# PowerSuply_Schematic_ETCautoPrikratki.net
KiCad netlist of a schematic drawn in EasyEDA
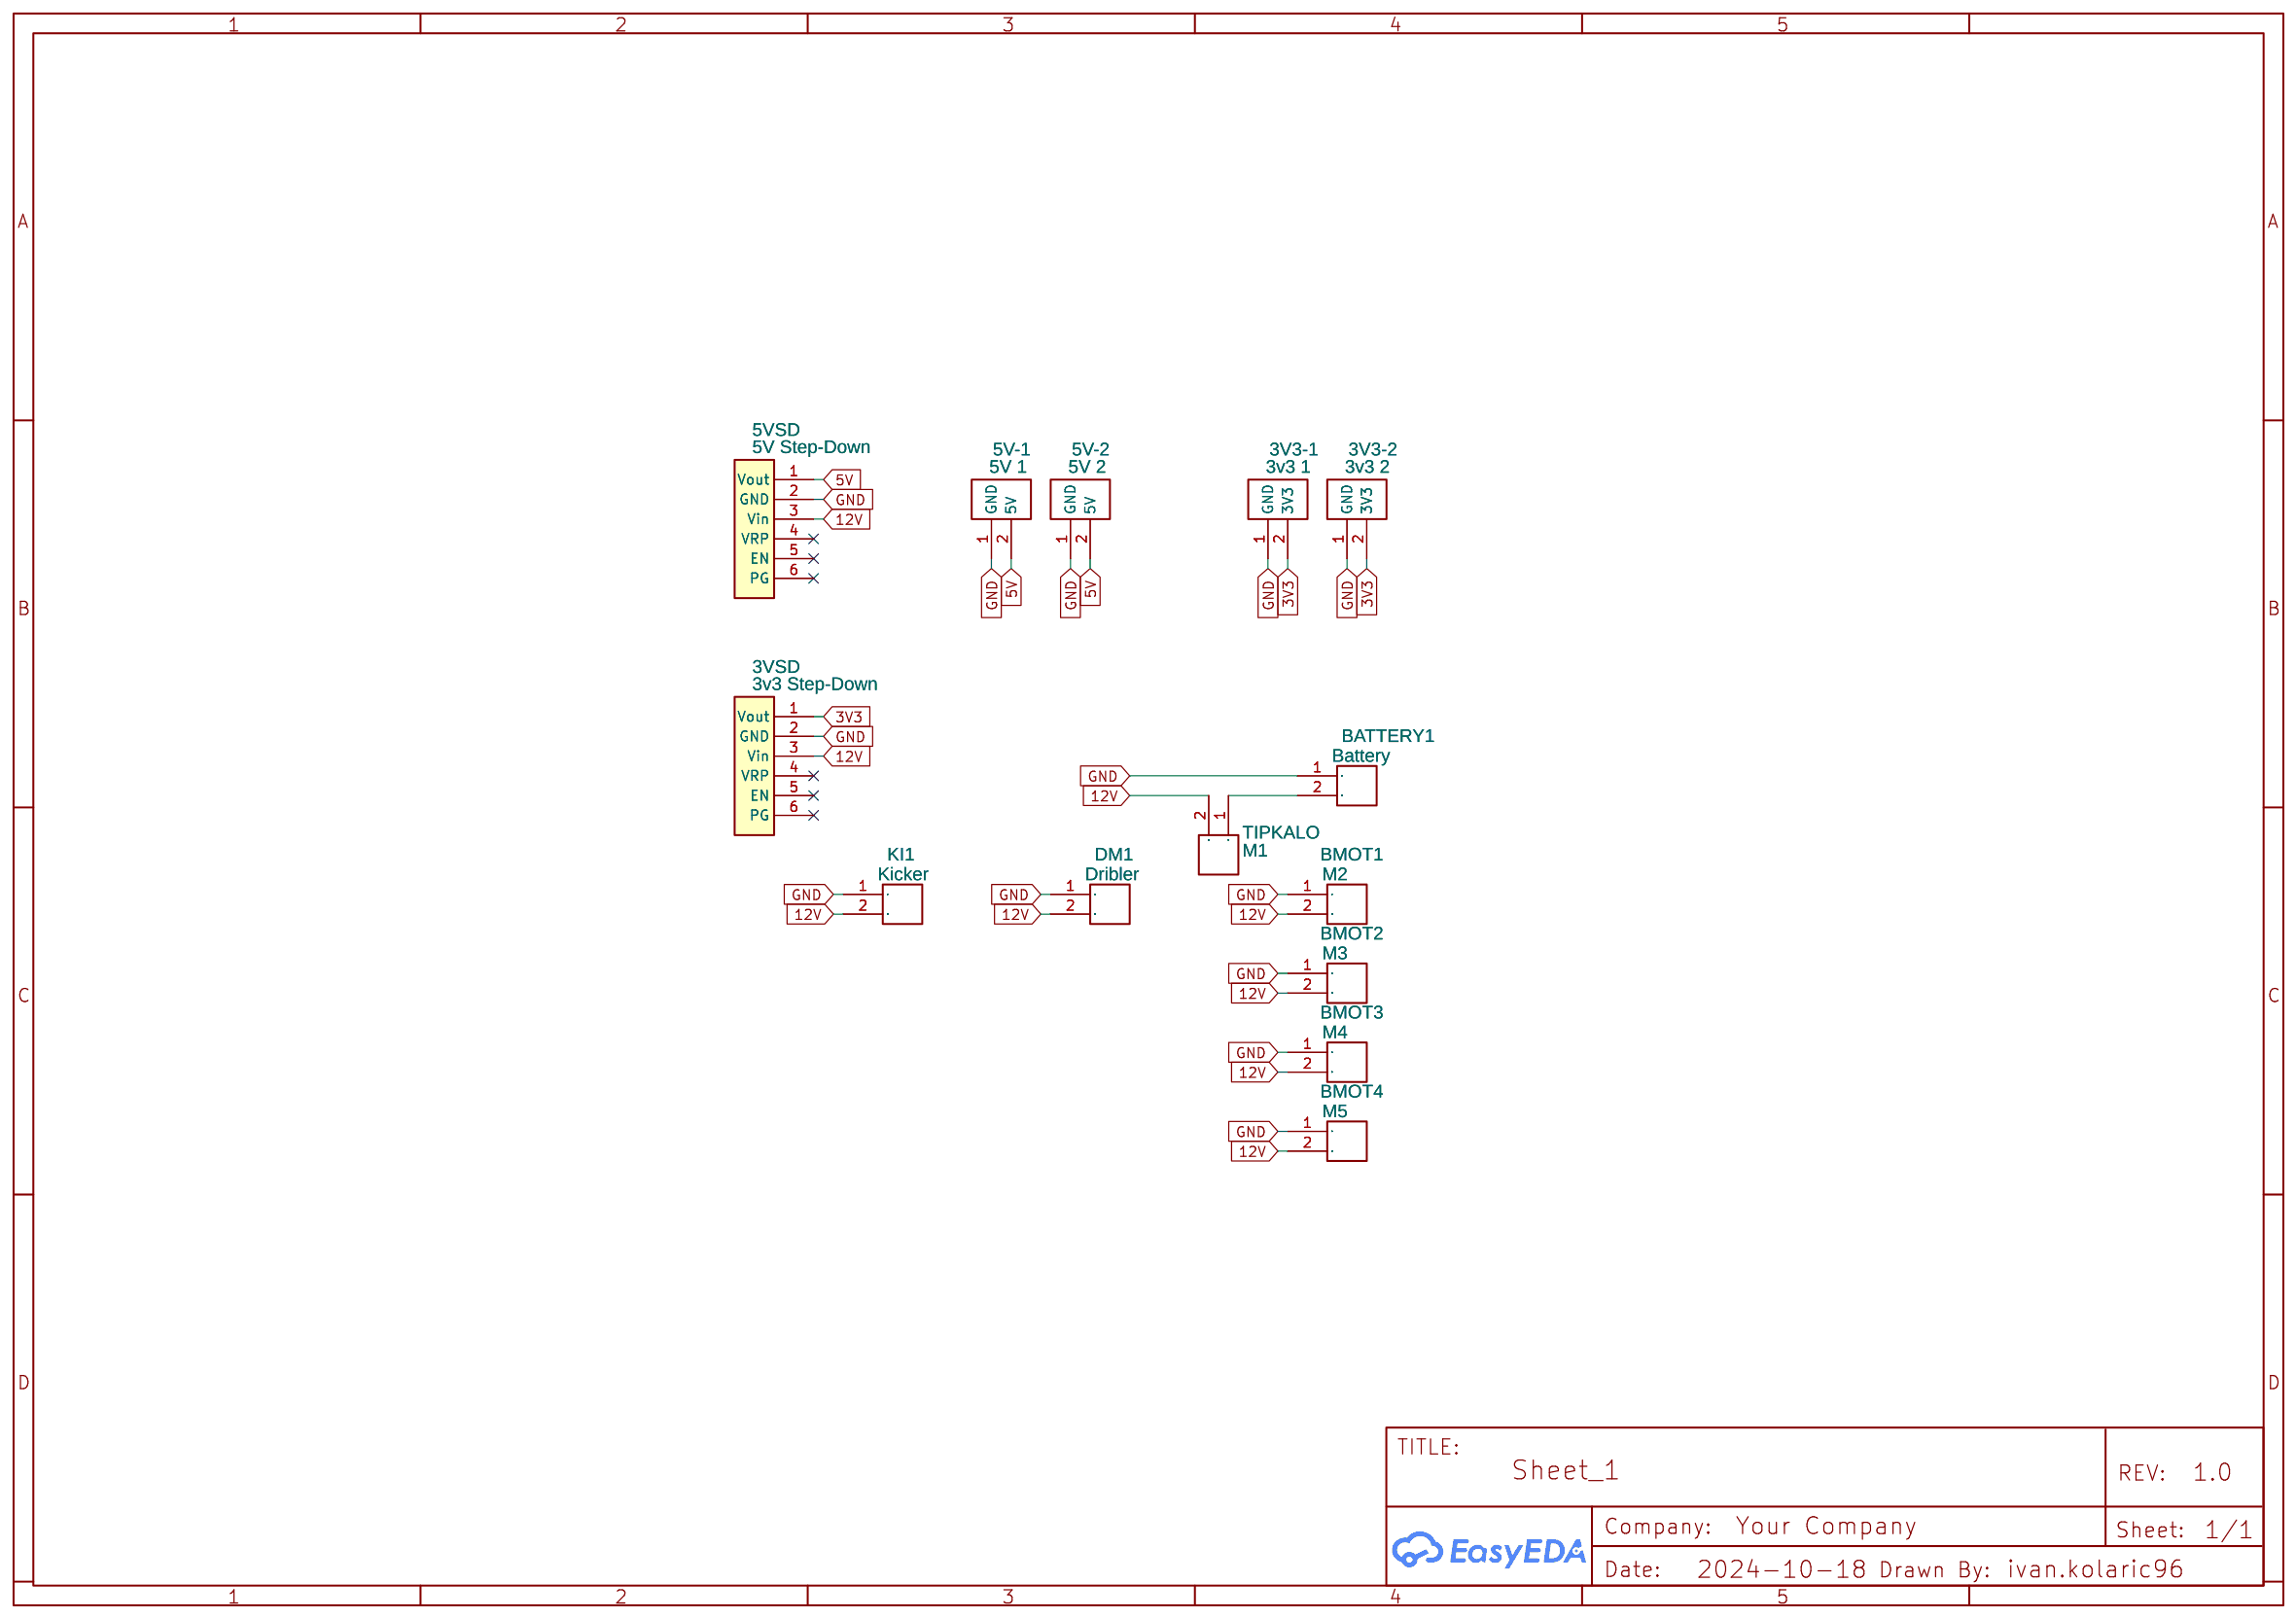
[diagram p0: schematic sheet]

(export (version "E")
  (design (tool "Eeschema 10.0.6"))
  (components
    (comp (ref "3V3-1")
      (value "3v3 1")
      (fields (field (name "Manufacturer Part") "22-11-2022") (field (name "Manufacturer") "MOLEX"))
      (libsource (lib "") (part "MOLEX_KK254_2P VERT._1"))
    )
    (comp (ref "3V3-2")
      (value "3v3 2")
      (fields (field (name "Manufacturer Part") "22-11-2022") (field (name "Manufacturer") "MOLEX"))
      (libsource (lib "") (part "MOLEX_KK254_2P VERT._1"))
    )
    (comp (ref "3VSD") (value "3v3 Step-Down") (libsource (lib "") (part "STEP-DOWN POLOLU D36V50F5_1")))
    (comp (ref "5V-1")
      (value "5V 1")
      (fields (field (name "Manufacturer Part") "22-11-2022") (field (name "Manufacturer") "MOLEX"))
      (libsource (lib "") (part "MOLEX_KK254_2P VERT."))
    )
    (comp (ref "5V-2")
      (value "5V 2")
      (fields (field (name "Manufacturer Part") "22-11-2022") (field (name "Manufacturer") "MOLEX"))
      (libsource (lib "") (part "MOLEX_KK254_2P VERT."))
    )
    (comp (ref "5VSD") (value "5V Step-Down") (libsource (lib "") (part "STEP-DOWN POLOLU D36V50F5")))
    (comp (ref "BATTERY1") (value "Battery") (libsource (lib "") (part "Molex KKK396 2 Pin_4")))
    (comp (ref "BMOT1") (value "M2") (libsource (lib "") (part "Molex KKK396 2 Pin_1")))
    (comp (ref "BMOT2") (value "M3") (libsource (lib "") (part "Molex KKK396 2 Pin_1")))
    (comp (ref "BMOT3") (value "M4") (libsource (lib "") (part "Molex KKK396 2 Pin_1")))
    (comp (ref "BMOT4") (value "M5") (libsource (lib "") (part "Molex KKK396 2 Pin_1")))
    (comp (ref "DM1") (value "Dribler") (libsource (lib "") (part "Molex KKK396 2 Pin")))
    (comp (ref "KI1") (value "Kicker") (libsource (lib "") (part "Molex KKK396 2 Pin_3")))
    (comp (ref "TIPKALO") (value "M1") (libsource (lib "") (part "Molex KKK396 2 Pin_2")))
  )
  (nets
    (net (code "1") (name "3V3") (class "Default")
      (node (ref "3V3-1") (pin "2") (pinfunction "3V3_2") (pintype "unspecified"))
      (node (ref "3V3-2") (pin "2") (pinfunction "3V3_2") (pintype "unspecified"))
      (node (ref "3VSD") (pin "1") (pinfunction "Vout_1") (pintype "unspecified"))
    )
    (net (code "2") (name "5V") (class "Default")
      (node (ref "5V-1") (pin "2") (pinfunction "5V_2") (pintype "unspecified"))
      (node (ref "5V-2") (pin "2") (pinfunction "5V_2") (pintype "unspecified"))
      (node (ref "5VSD") (pin "1") (pinfunction "Vout_1") (pintype "unspecified"))
    )
    (net (code "3") (name "12V") (class "Default")
      (node (ref "3VSD") (pin "3") (pinfunction "Vin_3") (pintype "unspecified"))
      (node (ref "5VSD") (pin "3") (pinfunction "Vin_3") (pintype "unspecified"))
      (node (ref "BMOT1") (pin "2") (pinfunction "2_2") (pintype "unspecified"))
      (node (ref "BMOT2") (pin "2") (pinfunction "2_2") (pintype "unspecified"))
      (node (ref "BMOT3") (pin "2") (pinfunction "2_2") (pintype "unspecified"))
      (node (ref "BMOT4") (pin "2") (pinfunction "2_2") (pintype "unspecified"))
      (node (ref "DM1") (pin "2") (pinfunction "2_2") (pintype "unspecified"))
      (node (ref "KI1") (pin "2") (pinfunction "2_2") (pintype "unspecified"))
      (node (ref "TIPKALO") (pin "2") (pinfunction "2_2") (pintype "unspecified"))
    )
    (net (code "4") (name "GND") (class "Default")
      (node (ref "3V3-1") (pin "1") (pinfunction "GND_1") (pintype "unspecified"))
      (node (ref "3V3-2") (pin "1") (pinfunction "GND_1") (pintype "unspecified"))
      (node (ref "3VSD") (pin "2") (pinfunction "GND_2") (pintype "unspecified"))
      (node (ref "5V-1") (pin "1") (pinfunction "GND_1") (pintype "unspecified"))
      (node (ref "5V-2") (pin "1") (pinfunction "GND_1") (pintype "unspecified"))
      (node (ref "5VSD") (pin "2") (pinfunction "GND_2") (pintype "unspecified"))
      (node (ref "BATTERY1") (pin "1") (pinfunction "1_1") (pintype "unspecified"))
      (node (ref "BMOT1") (pin "1") (pinfunction "1_1") (pintype "unspecified"))
      (node (ref "BMOT2") (pin "1") (pinfunction "1_1") (pintype "unspecified"))
      (node (ref "BMOT3") (pin "1") (pinfunction "1_1") (pintype "unspecified"))
      (node (ref "BMOT4") (pin "1") (pinfunction "1_1") (pintype "unspecified"))
      (node (ref "DM1") (pin "1") (pinfunction "1_1") (pintype "unspecified"))
      (node (ref "KI1") (pin "1") (pinfunction "1_1") (pintype "unspecified"))
    )
    (net (code "5") (name "Net-(BATTERY1-Pad2)") (class "Default")
      (node (ref "BATTERY1") (pin "2") (pinfunction "2_2") (pintype "unspecified"))
      (node (ref "TIPKALO") (pin "1") (pinfunction "1_1") (pintype "unspecified"))
    )
    (net (code "6") (name "unconnected-(3VSD-EN-Pad5)") (class "Default")
      (node (ref "3VSD") (pin "5") (pinfunction "EN_5") (pintype "unspecified+no_connect"))
    )
    (net (code "7") (name "unconnected-(3VSD-PG-Pad6)") (class "Default")
      (node (ref "3VSD") (pin "6") (pinfunction "PG_6") (pintype "unspecified+no_connect"))
    )
    (net (code "8") (name "unconnected-(3VSD-VRP-Pad4)") (class "Default")
      (node (ref "3VSD") (pin "4") (pinfunction "VRP_4") (pintype "unspecified+no_connect"))
    )
    (net (code "9") (name "unconnected-(5VSD-EN-Pad5)") (class "Default")
      (node (ref "5VSD") (pin "5") (pinfunction "EN_5") (pintype "unspecified+no_connect"))
    )
    (net (code "10") (name "unconnected-(5VSD-PG-Pad6)") (class "Default")
      (node (ref "5VSD") (pin "6") (pinfunction "PG_6") (pintype "unspecified+no_connect"))
    )
    (net (code "11") (name "unconnected-(5VSD-VRP-Pad4)") (class "Default")
      (node (ref "5VSD") (pin "4") (pinfunction "VRP_4") (pintype "unspecified+no_connect"))
    )
  )
)
